# Sheet1.net
KiCad netlist of a schematic drawn in Altium Designer
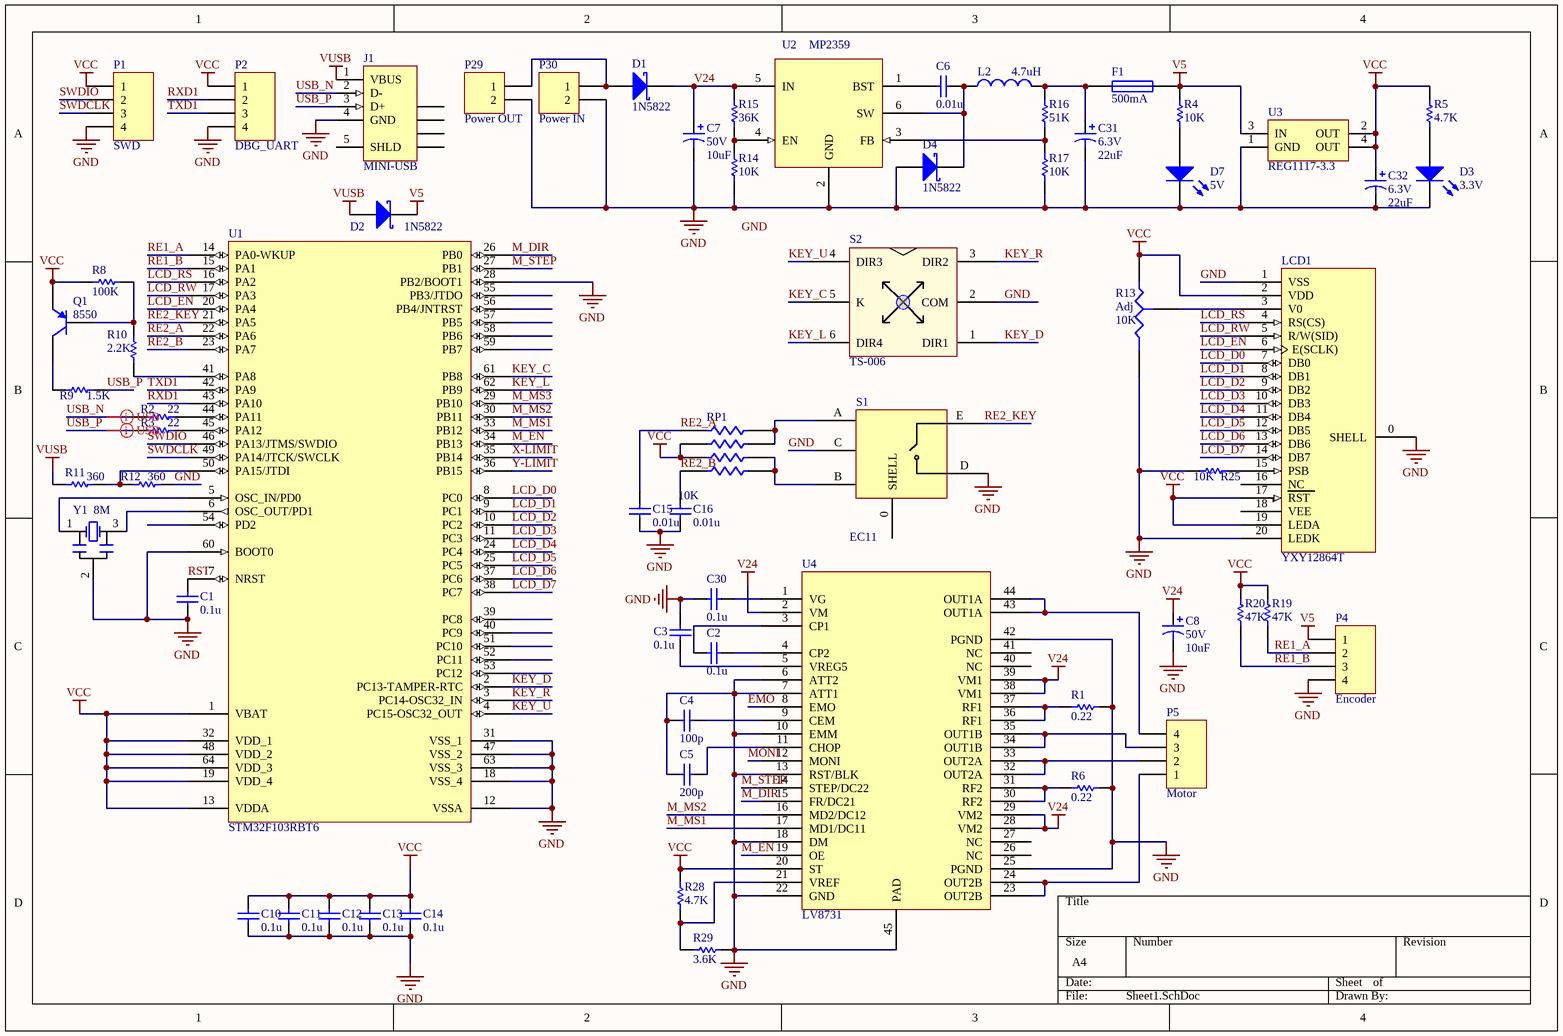
[diagram p0: Sheet1.SchDoc]

(export (version "E")
  (design (tool "Eeschema 10.0.6"))
  (components
    (comp (ref "C1")
      (value "0.1u")
      (footprint "C-1608[0603]")
      (description "Capacitor (Semiconductor SIM Model)")
      (fields (field (name "Comment") "Cap Semi") (field (name "PUBLISHER") "Altium Limited"))
      (libsource (lib "Miscellaneous Devices") (part "Cap Semi"))
    )
    (comp (ref "C2")
      (value "0.1u")
      (footprint "C-1608[0603]")
      (description "Capacitor (Semiconductor SIM Model)")
      (fields (field (name "Comment") "Cap Semi") (field (name "PUBLISHER") "Altium Limited"))
      (libsource (lib "Miscellaneous Devices") (part "Cap Semi"))
    )
    (comp (ref "C3")
      (value "0.1u")
      (footprint "C-1608[0603]")
      (description "Capacitor (Semiconductor SIM Model)")
      (fields (field (name "Comment") "Cap Semi") (field (name "PUBLISHER") "Altium Limited"))
      (libsource (lib "Miscellaneous Devices") (part "Cap Semi"))
    )
    (comp (ref "C4")
      (value "100p")
      (footprint "C-1608[0603]")
      (description "Capacitor (Semiconductor SIM Model)")
      (fields (field (name "Comment") "Cap Semi") (field (name "PUBLISHER") "Altium Limited"))
      (libsource (lib "Miscellaneous Devices") (part "Cap Semi"))
    )
    (comp (ref "C5")
      (value "200p")
      (footprint "C-1608[0603]")
      (description "Capacitor (Semiconductor SIM Model)")
      (fields (field (name "Comment") "Cap Semi") (field (name "PUBLISHER") "Altium Limited"))
      (libsource (lib "Miscellaneous Devices") (part "Cap Semi"))
    )
    (comp (ref "C6")
      (value "0.01u")
      (footprint "C-1608[0603]")
      (description "Capacitor (Semiconductor SIM Model)")
      (fields (field (name "Comment") "Cap Semi") (field (name "PUBLISHER") "Altium Limited"))
      (libsource (lib "Miscellaneous Devices") (part "Cap Semi"))
    )
    (comp (ref "C7")
      (value "50V")
      (footprint "RB.1/.25")
      (description "Polarized Capacitor (Radial)")
      (fields (field (name "ALTIUM_VALUE") "10uF") (field (name "PUBLISHER") "Altium Limited"))
      (libsource (lib "Miscellaneous Devices") (part "Cap Pol1"))
    )
    (comp (ref "C8")
      (value "50V")
      (footprint "RB.1/.25")
      (description "Polarized Capacitor (Radial)")
      (fields (field (name "ALTIUM_VALUE") "10uF") (field (name "PUBLISHER") "Altium Limited"))
      (libsource (lib "Miscellaneous Devices") (part "Cap Pol1"))
    )
    (comp (ref "C10")
      (value "0.1u")
      (footprint "C-1608[0603]")
      (description "Capacitor (Semiconductor SIM Model)")
      (fields (field (name "Comment") "Cap Semi") (field (name "PUBLISHER") "Altium Limited"))
      (libsource (lib "Miscellaneous Devices") (part "Cap Semi"))
    )
    (comp (ref "C11")
      (value "0.1u")
      (footprint "C-1608[0603]")
      (description "Capacitor (Semiconductor SIM Model)")
      (fields (field (name "Comment") "Cap Semi") (field (name "PUBLISHER") "Altium Limited"))
      (libsource (lib "Miscellaneous Devices") (part "Cap Semi"))
    )
    (comp (ref "C12")
      (value "0.1u")
      (footprint "C-1608[0603]")
      (description "Capacitor (Semiconductor SIM Model)")
      (fields (field (name "Comment") "Cap Semi") (field (name "PUBLISHER") "Altium Limited"))
      (libsource (lib "Miscellaneous Devices") (part "Cap Semi"))
    )
    (comp (ref "C13")
      (value "0.1u")
      (footprint "C-1608[0603]")
      (description "Capacitor (Semiconductor SIM Model)")
      (fields (field (name "Comment") "Cap Semi") (field (name "PUBLISHER") "Altium Limited"))
      (libsource (lib "Miscellaneous Devices") (part "Cap Semi"))
    )
    (comp (ref "C14")
      (value "0.1u")
      (footprint "C-1608[0603]")
      (description "Capacitor (Semiconductor SIM Model)")
      (fields (field (name "Comment") "Cap Semi") (field (name "PUBLISHER") "Altium Limited"))
      (libsource (lib "Miscellaneous Devices") (part "Cap Semi"))
    )
    (comp (ref "C15")
      (value "0.01u")
      (footprint "C-1608[0603]")
      (description "Capacitor (Semiconductor SIM Model)")
      (fields (field (name "Comment") "Cap Semi") (field (name "PUBLISHER") "Altium Limited"))
      (libsource (lib "Miscellaneous Devices") (part "Cap Semi"))
    )
    (comp (ref "C16")
      (value "0.01u")
      (footprint "C-1608[0603]")
      (description "Capacitor (Semiconductor SIM Model)")
      (fields (field (name "Comment") "Cap Semi") (field (name "PUBLISHER") "Altium Limited"))
      (libsource (lib "Miscellaneous Devices") (part "Cap Semi"))
    )
    (comp (ref "C30")
      (value "0.1u")
      (footprint "C-1608[0603]")
      (description "Capacitor (Semiconductor SIM Model)")
      (fields (field (name "Comment") "Cap Semi") (field (name "PUBLISHER") "Altium Limited"))
      (libsource (lib "Miscellaneous Devices") (part "Cap Semi"))
    )
    (comp (ref "C31")
      (value "6.3V")
      (footprint "C-2012[0805]")
      (description "Tantalum capacitor")
      (fields (field (name "ALTIUM_VALUE") "22uF") (field (name "PUBLISHER") "Altium Limited"))
      (libsource (lib "Miscellaneous Devices") (part "Cap Pol3"))
    )
    (comp (ref "C32")
      (value "6.3V")
      (footprint "C-2012[0805]")
      (description "Tantalum capacitor")
      (fields (field (name "ALTIUM_VALUE") "22uF") (field (name "PUBLISHER") "Altium Limited"))
      (libsource (lib "Miscellaneous Devices") (part "Cap Pol3"))
    )
    (comp (ref "D1")
      (value "1N5822")
      (footprint "DO-214AC")
      (description "Schottky Diode")
      (fields (field (name "PUBLISHER") "Altium Limited"))
      (libsource (lib "Miscellaneous Devices") (part "D Schottky"))
    )
    (comp (ref "D2")
      (value "1N5822")
      (footprint "DO-214AC")
      (description "Schottky Diode")
      (fields (field (name "PUBLISHER") "Altium Limited"))
      (libsource (lib "Miscellaneous Devices") (part "D Schottky"))
    )
    (comp (ref "D3")
      (value "3.3V")
      (footprint "LED_0805_RED")
      (description "Typical RED, GREEN, YELLOW, AMBER GaAs LED")
      (fields (field (name "PUBLISHER") "Altium Limited"))
      (libsource (lib "Miscellaneous Devices") (part "LED2"))
    )
    (comp (ref "D4")
      (value "1N5822")
      (footprint "DO-214AC")
      (description "Schottky Diode")
      (fields (field (name "PUBLISHER") "Altium Limited"))
      (libsource (lib "Miscellaneous Devices") (part "D Schottky"))
    )
    (comp (ref "D7")
      (value "5V")
      (footprint "LED_0805_RED")
      (description "Typical RED, GREEN, YELLOW, AMBER GaAs LED")
      (fields (field (name "PUBLISHER") "Altium Limited"))
      (libsource (lib "Miscellaneous Devices") (part "LED2"))
    )
    (comp (ref "F1")
      (value "500mA")
      (footprint "2012[0805]")
      (description "Fuse")
      (fields (field (name "PUBLISHER") "Altium Limited"))
      (libsource (lib "Miscellaneous Devices") (part "Fuse 1"))
    )
    (comp (ref "J1")
      (value "MINI-USB")
      (footprint "Mini USB 3D")
      (description "USB 2.0, Right Angle, SMT, A Type, Receptacle, 5 Position, Black")
      (fields (field (name "PUBLISHER") "Altium Limited"))
      (libsource (lib "AMP Serial Bus USB") (part "440478-1"))
    )
    (comp (ref "L2")
      (value "4.7uH")
      (footprint "L-5845")
      (description "Inductor")
      (fields (field (name "PUBLISHER") "Altium Limited"))
      (libsource (lib "Miscellaneous Devices") (part "Inductor"))
    )
    (comp (ref "LCD1")
      (value "YXY12864T")
      (footprint "12864T")
      (libsource (lib "Schlib1") (part "YXY12864T"))
    )
    (comp (ref "P1")
      (value "SWD")
      (footprint "HDR1X4")
      (description "Header, 4-Pin")
      (fields (field (name "PUBLISHER") "Altium Limited"))
      (libsource (lib "Miscellaneous Connectors") (part "Header 4"))
    )
    (comp (ref "P2")
      (value "DBG_UART")
      (footprint "HDR1X4")
      (description "Header, 4-Pin")
      (fields (field (name "PUBLISHER") "Altium Limited"))
      (libsource (lib "Miscellaneous Connectors") (part "Header 4"))
    )
    (comp (ref "P4")
      (value "Encoder")
      (footprint "HDR1X4H")
      (description "Header, 4-Pin, Right Angle")
      (fields (field (name "PUBLISHER") "Altium Limited"))
      (libsource (lib "Miscellaneous Connectors") (part "Header 4H"))
    )
    (comp (ref "P5")
      (value "Motor")
      (footprint "HDR1X4H")
      (description "Header, 4-Pin, Right Angle")
      (fields (field (name "PUBLISHER") "Altium Limited"))
      (libsource (lib "") (part "Header 4H_1"))
    )
    (comp (ref "P29")
      (value "Power OUT")
      (footprint "DC_POWER")
      (description "Header, 2-Pin")
      (fields (field (name "PUBLISHER") "Altium Limited"))
      (libsource (lib "Miscellaneous Connectors") (part "MHDR1X2"))
    )
    (comp (ref "P30")
      (value "Power IN")
      (footprint "DC_POWER")
      (description "Header, 2-Pin")
      (fields (field (name "PUBLISHER") "Altium Limited"))
      (libsource (lib "Miscellaneous Connectors") (part "MHDR1X2"))
    )
    (comp (ref "Q1")
      (value "8550")
      (footprint "SOT23B")
      (description "PNP Bipolar Transistor")
      (fields (field (name "PUBLISHER") "Altium Limited"))
      (libsource (lib "Miscellaneous Devices") (part "PNP"))
    )
    (comp (ref "R1")
      (value "0.22")
      (footprint "R-6332[2512]")
      (description "Semiconductor Resistor")
      (fields (field (name "Comment") "Res Semi") (field (name "PUBLISHER") "Altium Limited"))
      (libsource (lib "Miscellaneous Devices") (part "Res Semi"))
    )
    (comp (ref "R2")
      (value "22")
      (footprint "R-1608[0603]")
      (description "Semiconductor Resistor")
      (fields (field (name "Comment") "Res Semi") (field (name "PUBLISHER") "Altium Limited"))
      (libsource (lib "Miscellaneous Devices") (part "Res Semi"))
    )
    (comp (ref "R3")
      (value "22")
      (footprint "R-1608[0603]")
      (description "Semiconductor Resistor")
      (fields (field (name "Comment") "Res Semi") (field (name "PUBLISHER") "Altium Limited"))
      (libsource (lib "Miscellaneous Devices") (part "Res Semi"))
    )
    (comp (ref "R4")
      (value "10K")
      (footprint "R-1608[0603]")
      (description "Semiconductor Resistor")
      (fields (field (name "Comment") "Res Semi") (field (name "PUBLISHER") "Altium Limited"))
      (libsource (lib "Miscellaneous Devices") (part "Res Semi"))
    )
    (comp (ref "R5")
      (value "4.7K")
      (footprint "R-1608[0603]")
      (description "Semiconductor Resistor")
      (fields (field (name "Comment") "Res Semi") (field (name "PUBLISHER") "Altium Limited"))
      (libsource (lib "Miscellaneous Devices") (part "Res Semi"))
    )
    (comp (ref "R6")
      (value "0.22")
      (footprint "R-6332[2512]")
      (description "Semiconductor Resistor")
      (fields (field (name "Comment") "Res Semi") (field (name "PUBLISHER") "Altium Limited"))
      (libsource (lib "Miscellaneous Devices") (part "Res Semi"))
    )
    (comp (ref "R8")
      (value "100K")
      (footprint "R-1608[0603]")
      (description "Semiconductor Resistor")
      (fields (field (name "Comment") "Res Semi") (field (name "PUBLISHER") "Altium Limited"))
      (libsource (lib "Miscellaneous Devices") (part "Res Semi"))
    )
    (comp (ref "R9")
      (value "1.5K")
      (footprint "R-1608[0603]")
      (description "Semiconductor Resistor")
      (fields (field (name "Comment") "Res Semi") (field (name "PUBLISHER") "Altium Limited"))
      (libsource (lib "Miscellaneous Devices") (part "Res Semi"))
    )
    (comp (ref "R10")
      (value "2.2K")
      (footprint "R-1608[0603]")
      (description "Semiconductor Resistor")
      (fields (field (name "Comment") "Res Semi") (field (name "PUBLISHER") "Altium Limited"))
      (libsource (lib "Miscellaneous Devices") (part "Res Semi"))
    )
    (comp (ref "R11")
      (value "360")
      (footprint "R-1608[0603]")
      (description "Semiconductor Resistor")
      (fields (field (name "Comment") "Res Semi") (field (name "PUBLISHER") "Altium Limited"))
      (libsource (lib "Miscellaneous Devices") (part "Res Semi"))
    )
    (comp (ref "R12")
      (value "360")
      (footprint "R-1608[0603]")
      (description "Semiconductor Resistor")
      (fields (field (name "Comment") "Res Semi") (field (name "PUBLISHER") "Altium Limited"))
      (libsource (lib "Miscellaneous Devices") (part "Res Semi"))
    )
    (comp (ref "R13")
      (value "Adj")
      (footprint "HDR1X3")
      (description "Tapped Resistor")
      (fields (field (name "ALTIUM_VALUE") "10K") (field (name "PUBLISHER") "Altium Limited"))
      (libsource (lib "Miscellaneous Devices") (part "Res Tap"))
    )
    (comp (ref "R14")
      (value "10K")
      (footprint "R-1608[0603]")
      (description "Semiconductor Resistor")
      (fields (field (name "Comment") "Res Semi") (field (name "PUBLISHER") "Altium Limited"))
      (libsource (lib "Miscellaneous Devices") (part "Res Semi"))
    )
    (comp (ref "R15")
      (value "36K")
      (footprint "R-1608[0603]")
      (description "Semiconductor Resistor")
      (fields (field (name "Comment") "Res Semi") (field (name "PUBLISHER") "Altium Limited"))
      (libsource (lib "Miscellaneous Devices") (part "Res Semi"))
    )
    (comp (ref "R16")
      (value "51K")
      (footprint "R-1608[0603]")
      (description "Semiconductor Resistor")
      (fields (field (name "Comment") "Res Semi") (field (name "PUBLISHER") "Altium Limited"))
      (libsource (lib "Miscellaneous Devices") (part "Res Semi"))
    )
    (comp (ref "R17")
      (value "10K")
      (footprint "R-1608[0603]")
      (description "Semiconductor Resistor")
      (fields (field (name "Comment") "Res Semi") (field (name "PUBLISHER") "Altium Limited"))
      (libsource (lib "Miscellaneous Devices") (part "Res Semi"))
    )
    (comp (ref "R19")
      (value "47K")
      (footprint "R-1608[0603]")
      (description "Semiconductor Resistor")
      (fields (field (name "Comment") "Res Semi") (field (name "PUBLISHER") "Altium Limited"))
      (libsource (lib "Miscellaneous Devices") (part "Res Semi"))
    )
    (comp (ref "R20")
      (value "47K")
      (footprint "R-1608[0603]")
      (description "Semiconductor Resistor")
      (fields (field (name "Comment") "Res Semi") (field (name "PUBLISHER") "Altium Limited"))
      (libsource (lib "Miscellaneous Devices") (part "Res Semi"))
    )
    (comp (ref "R25")
      (value "10K")
      (footprint "R-1608[0603]")
      (description "Semiconductor Resistor")
      (fields (field (name "Comment") "Res Semi") (field (name "PUBLISHER") "Altium Limited"))
      (libsource (lib "Miscellaneous Devices") (part "Res Semi"))
    )
    (comp (ref "R28")
      (value "4.7K")
      (footprint "R-1608[0603]")
      (description "Semiconductor Resistor")
      (fields (field (name "Comment") "Res Semi") (field (name "PUBLISHER") "Altium Limited"))
      (libsource (lib "Miscellaneous Devices") (part "Res Semi"))
    )
    (comp (ref "R29")
      (value "3.6K")
      (footprint "R-1608[0603]")
      (description "Semiconductor Resistor")
      (fields (field (name "Comment") "Res Semi") (field (name "PUBLISHER") "Altium Limited"))
      (libsource (lib "Miscellaneous Devices") (part "Res Semi"))
    )
    (comp (ref "RP1")
      (value "10K")
      (footprint "R0603x4")
      (fields (field (name "Comment") "4xRes"))
      (libsource (lib "Schlib1") (part "RPACK4"))
    )
    (comp (ref "S1") (value "EC11") (footprint "EC11") (libsource (lib "Schlib1") (part "EC11")))
    (comp (ref "S2") (value "TS-006") (footprint "TS-006") (libsource (lib "Schlib1") (part "TS-006")))
    (comp (ref "U1")
      (value "STM32F103RBT6")
      (footprint "LQFP64_N")
      (description "STM32 ARM-based 32-bit MCU High-density")
      (fields (field (name "PUBLISHER") "Altium Limited"))
      (libsource (lib "ST Microcontroller 32-Bit STM32") (part "STM32F103RBT6"))
    )
    (comp (ref "U2")
      (value "MP2359")
      (footprint "SOT23-6")
      (description "1.2A, 24V, 1.4MHz  Step-Down Converter")
      (libsource (lib "Schlib1") (part "MP2359"))
    )
    (comp (ref "U3")
      (value "REG1117-3.3")
      (footprint "SOT223-3D")
      (description "800mA and 1A Low Dropout Positive Regulator 2.85V, 3.3V, 5V, and Adjustable")
      (fields (field (name "PUBLISHER") "Altium Limited"))
      (libsource (lib "BB Power Mgt Voltage Regulator") (part "REG1117-3.3"))
    )
    (comp (ref "U4") (value "LV8731") (footprint "LV8731_V3") (libsource (lib "Schlib1") (part "LV8731")))
    (comp (ref "Y1")
      (value "8M")
      (footprint "Crystal_C")
      (description "Crystal Oscillator")
      (fields (field (name "PUBLISHER") "Altium Limited"))
      (libsource (lib "Schlib1") (part "XTAL_C"))
    )
  )
  (nets
    (net (code "1") (name "/EMO") (class "Default")
      (node (ref "U4") (pin "8") (pinfunction "EMO_8") (pintype "passive"))
    )
    (net (code "2") (name "/KEY_C") (class "Default")
      (node (ref "S2") (pin "5") (pinfunction "K_5") (pintype "passive"))
      (node (ref "U1") (pin "61") (pinfunction "PB8_61") (pintype "bidirectional"))
    )
    (net (code "3") (name "/KEY_D") (class "Default")
      (node (ref "S2") (pin "1") (pinfunction "DIR1_1") (pintype "passive"))
      (node (ref "U1") (pin "2") (pinfunction "PC13-TAMPER-RTC_2") (pintype "bidirectional"))
    )
    (net (code "4") (name "/KEY_L") (class "Default")
      (node (ref "S2") (pin "6") (pinfunction "DIR4_6") (pintype "passive"))
      (node (ref "U1") (pin "62") (pinfunction "PB9_62") (pintype "bidirectional"))
    )
    (net (code "5") (name "/KEY_R") (class "Default")
      (node (ref "S2") (pin "3") (pinfunction "DIR2_3") (pintype "passive"))
      (node (ref "U1") (pin "3") (pinfunction "PC14-OSC32_IN_3") (pintype "bidirectional"))
    )
    (net (code "6") (name "/KEY_U") (class "Default")
      (node (ref "S2") (pin "4") (pinfunction "DIR3_4") (pintype "passive"))
      (node (ref "U1") (pin "4") (pinfunction "PC15-OSC32_OUT_4") (pintype "bidirectional"))
    )
    (net (code "7") (name "/LCD_D0") (class "Default")
      (node (ref "LCD1") (pin "7") (pinfunction "DB0_7") (pintype "bidirectional"))
      (node (ref "U1") (pin "8") (pinfunction "PC0_8") (pintype "bidirectional"))
    )
    (net (code "8") (name "/LCD_D1") (class "Default")
      (node (ref "LCD1") (pin "8") (pinfunction "DB1_8") (pintype "bidirectional"))
      (node (ref "U1") (pin "9") (pinfunction "PC1_9") (pintype "bidirectional"))
    )
    (net (code "9") (name "/LCD_D2") (class "Default")
      (node (ref "LCD1") (pin "9") (pinfunction "DB2_9") (pintype "bidirectional"))
      (node (ref "U1") (pin "10") (pinfunction "PC2_10") (pintype "bidirectional"))
    )
    (net (code "10") (name "/LCD_D3") (class "Default")
      (node (ref "LCD1") (pin "10") (pinfunction "DB3_10") (pintype "bidirectional"))
      (node (ref "U1") (pin "11") (pinfunction "PC3_11") (pintype "bidirectional"))
    )
    (net (code "11") (name "/LCD_D4") (class "Default")
      (node (ref "LCD1") (pin "11") (pinfunction "DB4_11") (pintype "bidirectional"))
      (node (ref "U1") (pin "24") (pinfunction "PC4_24") (pintype "bidirectional"))
    )
    (net (code "12") (name "/LCD_D5") (class "Default")
      (node (ref "LCD1") (pin "12") (pinfunction "DB5_12") (pintype "bidirectional"))
      (node (ref "U1") (pin "25") (pinfunction "PC5_25") (pintype "bidirectional"))
    )
    (net (code "13") (name "/LCD_D6") (class "Default")
      (node (ref "LCD1") (pin "13") (pinfunction "DB6_13") (pintype "bidirectional"))
      (node (ref "U1") (pin "37") (pinfunction "PC6_37") (pintype "bidirectional"))
    )
    (net (code "14") (name "/LCD_D7") (class "Default")
      (node (ref "LCD1") (pin "14") (pinfunction "DB7_14") (pintype "bidirectional"))
      (node (ref "U1") (pin "38") (pinfunction "PC7_38") (pintype "bidirectional"))
    )
    (net (code "15") (name "/LCD_EN") (class "Default")
      (node (ref "LCD1") (pin "6") (pinfunction "E(SCLK)_6") (pintype "input"))
      (node (ref "U1") (pin "20") (pinfunction "PA4_20") (pintype "bidirectional"))
    )
    (net (code "16") (name "/LCD_RS") (class "Default")
      (node (ref "LCD1") (pin "4") (pinfunction "RS(CS)_4") (pintype "input"))
      (node (ref "U1") (pin "16") (pinfunction "PA2_16") (pintype "bidirectional"))
    )
    (net (code "17") (name "/LCD_RW") (class "Default")
      (node (ref "LCD1") (pin "5") (pinfunction "R/W(SID)_5") (pintype "input"))
      (node (ref "U1") (pin "17") (pinfunction "PA3_17") (pintype "bidirectional"))
    )
    (net (code "18") (name "/MONI") (class "Default")
      (node (ref "U4") (pin "12") (pinfunction "MONI_12") (pintype "passive"))
    )
    (net (code "19") (name "/M_DIR") (class "Default")
      (node (ref "U1") (pin "26") (pinfunction "PB0_26") (pintype "bidirectional"))
      (node (ref "U4") (pin "15") (pinfunction "FR/DC21_15") (pintype "passive"))
    )
    (net (code "20") (name "/M_EN") (class "Default")
      (node (ref "U1") (pin "34") (pinfunction "PB13_34") (pintype "bidirectional"))
      (node (ref "U4") (pin "19") (pinfunction "OE_19") (pintype "passive"))
    )
    (net (code "21") (name "/M_MS1") (class "Default")
      (node (ref "U1") (pin "33") (pinfunction "PB12_33") (pintype "bidirectional"))
      (node (ref "U4") (pin "17") (pinfunction "MD1/DC11_17") (pintype "passive"))
    )
    (net (code "22") (name "/M_MS2") (class "Default")
      (node (ref "U1") (pin "30") (pinfunction "PB11_30") (pintype "bidirectional"))
      (node (ref "U4") (pin "16") (pinfunction "MD2/DC12_16") (pintype "passive"))
    )
    (net (code "23") (name "/M_MS3") (class "Default")
      (node (ref "U1") (pin "29") (pinfunction "PB10_29") (pintype "bidirectional"))
    )
    (net (code "24") (name "/M_STEP") (class "Default")
      (node (ref "U1") (pin "27") (pinfunction "PB1_27") (pintype "bidirectional"))
      (node (ref "U4") (pin "14") (pinfunction "STEP/DC22_14") (pintype "passive"))
    )
    (net (code "25") (name "/RE1_A") (class "Default")
      (node (ref "P4") (pin "2") (pinfunction "2_2") (pintype "passive"))
      (node (ref "R19") (pin "1") (pinfunction "1_1") (pintype "passive"))
      (node (ref "U1") (pin "14") (pinfunction "PA0-WKUP_14") (pintype "bidirectional"))
    )
    (net (code "26") (name "/RE1_B") (class "Default")
      (node (ref "P4") (pin "3") (pinfunction "3_3") (pintype "passive"))
      (node (ref "R20") (pin "1") (pinfunction "1_1") (pintype "passive"))
      (node (ref "U1") (pin "15") (pinfunction "PA1_15") (pintype "bidirectional"))
    )
    (net (code "27") (name "/RE2_A") (class "Default")
      (node (ref "C15") (pin "2") (pinfunction "2_2") (pintype "passive"))
      (node (ref "RP1") (pin "5") (pinfunction "5_5") (pintype "passive"))
      (node (ref "U1") (pin "22") (pinfunction "PA6_22") (pintype "bidirectional"))
    )
    (net (code "28") (name "/RE2_B") (class "Default")
      (node (ref "C16") (pin "2") (pinfunction "2_2") (pintype "passive"))
      (node (ref "RP1") (pin "8") (pinfunction "8_8") (pintype "passive"))
      (node (ref "U1") (pin "23") (pinfunction "PA7_23") (pintype "bidirectional"))
    )
    (net (code "29") (name "/RE2_KEY") (class "Default")
      (node (ref "S1") (pin "E") (pinfunction "25_E") (pintype "passive"))
      (node (ref "U1") (pin "21") (pinfunction "PA5_21") (pintype "bidirectional"))
    )
    (net (code "30") (name "/RST") (class "Default")
      (node (ref "C1") (pin "2") (pinfunction "2_2") (pintype "passive"))
      (node (ref "U1") (pin "7") (pinfunction "NRST_7") (pintype "bidirectional"))
    )
    (net (code "31") (name "/RXD1") (class "Default")
      (node (ref "P2") (pin "2") (pinfunction "2_2") (pintype "passive"))
      (node (ref "U1") (pin "43") (pinfunction "PA10_43") (pintype "bidirectional"))
    )
    (net (code "32") (name "/SWDCLK") (class "Default")
      (node (ref "P1") (pin "3") (pinfunction "3_3") (pintype "passive"))
      (node (ref "U1") (pin "49") (pinfunction "PA14/JTCK/SWCLK_49") (pintype "bidirectional"))
    )
    (net (code "33") (name "/SWDIO") (class "Default")
      (node (ref "P1") (pin "2") (pinfunction "2_2") (pintype "passive"))
      (node (ref "U1") (pin "46") (pinfunction "PA13/JTMS/SWDIO_46") (pintype "bidirectional"))
    )
    (net (code "34") (name "/TXD1") (class "Default")
      (node (ref "P2") (pin "3") (pinfunction "3_3") (pintype "passive"))
      (node (ref "U1") (pin "42") (pinfunction "PA9_42") (pintype "bidirectional"))
    )
    (net (code "35") (name "/USB_N") (class "Default")
      (node (ref "J1") (pin "2") (pinfunction "D-_2") (pintype "input"))
      (node (ref "R2") (pin "1") (pinfunction "1_1") (pintype "passive"))
    )
    (net (code "36") (name "/USB_P") (class "Default")
      (node (ref "J1") (pin "3") (pinfunction "D+_3") (pintype "input"))
      (node (ref "R3") (pin "1") (pinfunction "1_1") (pintype "passive"))
      (node (ref "R9") (pin "1") (pinfunction "1_1") (pintype "passive"))
    )
    (net (code "37") (name "/X-LIMIT") (class "Default")
      (node (ref "U1") (pin "35") (pinfunction "PB14_35") (pintype "bidirectional"))
    )
    (net (code "38") (name "/Y-LIMIT") (class "Default")
      (node (ref "U1") (pin "36") (pinfunction "PB15_36") (pintype "bidirectional"))
    )
    (net (code "39") (name "GND") (class "Default")
      (node (ref "C1") (pin "1") (pinfunction "1_1") (pintype "passive"))
      (node (ref "C10") (pin "1") (pinfunction "1_1") (pintype "passive"))
      (node (ref "C11") (pin "1") (pinfunction "1_1") (pintype "passive"))
      (node (ref "C12") (pin "1") (pinfunction "1_1") (pintype "passive"))
      (node (ref "C13") (pin "1") (pinfunction "1_1") (pintype "passive"))
      (node (ref "C14") (pin "1") (pinfunction "1_1") (pintype "passive"))
      (node (ref "C15") (pin "1") (pinfunction "1_1") (pintype "passive"))
      (node (ref "C16") (pin "1") (pinfunction "1_1") (pintype "passive"))
      (node (ref "C3") (pin "2") (pinfunction "2_2") (pintype "passive"))
      (node (ref "C30") (pin "2") (pinfunction "2_2") (pintype "passive"))
      (node (ref "C31") (pin "2") (pinfunction "2_2") (pintype "passive"))
      (node (ref "C32") (pin "2") (pinfunction "2_2") (pintype "passive"))
      (node (ref "C4") (pin "1") (pinfunction "1_1") (pintype "passive"))
      (node (ref "C5") (pin "1") (pinfunction "1_1") (pintype "passive"))
      (node (ref "C7") (pin "2") (pinfunction "2_2") (pintype "passive"))
      (node (ref "C8") (pin "2") (pinfunction "2_2") (pintype "passive"))
      (node (ref "D3") (pin "2") (pinfunction "K_2") (pintype "passive"))
      (node (ref "D4") (pin "1") (pinfunction "A_1") (pintype "passive"))
      (node (ref "D7") (pin "2") (pinfunction "K_2") (pintype "passive"))
      (node (ref "J1") (pin "4") (pinfunction "GND_4") (pintype "power_in"))
      (node (ref "LCD1") (pin "0") (pinfunction "SHELL_0") (pintype "power_in"))
      (node (ref "LCD1") (pin "1") (pinfunction "VSS_1") (pintype "power_in"))
      (node (ref "LCD1") (pin "20") (pinfunction "LEDK_20") (pintype "power_in"))
      (node (ref "P1") (pin "4") (pinfunction "4_4") (pintype "passive"))
      (node (ref "P2") (pin "4") (pinfunction "4_4") (pintype "passive"))
      (node (ref "P29") (pin "2") (pinfunction "2_2") (pintype "passive"))
      (node (ref "P30") (pin "2") (pinfunction "2_2") (pintype "passive"))
      (node (ref "P4") (pin "4") (pinfunction "4_4") (pintype "passive"))
      (node (ref "R1") (pin "1") (pinfunction "1_1") (pintype "passive"))
      (node (ref "R12") (pin "1") (pinfunction "1_1") (pintype "passive"))
      (node (ref "R13") (pin "2") (pinfunction "B_2") (pintype "passive"))
      (node (ref "R14") (pin "1") (pinfunction "1_1") (pintype "passive"))
      (node (ref "R17") (pin "1") (pinfunction "1_1") (pintype "passive"))
      (node (ref "R25") (pin "2") (pinfunction "2_2") (pintype "passive"))
      (node (ref "R29") (pin "1") (pinfunction "1_1") (pintype "passive"))
      (node (ref "R6") (pin "1") (pinfunction "1_1") (pintype "passive"))
      (node (ref "S1") (pin "C") (pinfunction "C_C") (pintype "passive"))
      (node (ref "S1") (pin "D") (pinfunction "D_D") (pintype "passive"))
      (node (ref "S2") (pin "2") (pinfunction "COM_2") (pintype "passive"))
      (node (ref "U1") (pin "12") (pinfunction "VSSA_12") (pintype "power_in"))
      (node (ref "U1") (pin "18") (pinfunction "VSS_4_18") (pintype "power_in"))
      (node (ref "U1") (pin "28") (pinfunction "PB2/BOOT1_28") (pintype "bidirectional"))
      (node (ref "U1") (pin "31") (pinfunction "VSS_1_31") (pintype "power_in"))
      (node (ref "U1") (pin "47") (pinfunction "VSS_2_47") (pintype "power_in"))
      (node (ref "U1") (pin "60") (pinfunction "BOOT0_60") (pintype "input"))
      (node (ref "U1") (pin "63") (pinfunction "VSS_3_63") (pintype "power_in"))
      (node (ref "U2") (pin "2") (pinfunction "GND_2") (pintype "passive"))
      (node (ref "U3") (pin "1") (pinfunction "GND_1") (pintype "power_in"))
      (node (ref "U4") (pin "10") (pinfunction "EMM_10") (pintype "passive"))
      (node (ref "U4") (pin "13") (pinfunction "RST/BLK_13") (pintype "passive"))
      (node (ref "U4") (pin "18") (pinfunction "DM_18") (pintype "passive"))
      (node (ref "U4") (pin "22") (pinfunction "GND_22") (pintype "passive"))
      (node (ref "U4") (pin "25") (pinfunction "PGND_25") (pintype "passive"))
      (node (ref "U4") (pin "42") (pinfunction "PGND_42") (pintype "passive"))
      (node (ref "U4") (pin "45") (pinfunction "PAD_45") (pintype "passive"))
      (node (ref "U4") (pin "6") (pinfunction "ATT2_6") (pintype "passive"))
      (node (ref "U4") (pin "7") (pinfunction "ATT1_7") (pintype "passive"))
      (node (ref "Y1") (pin "2") (pinfunction "GND_2") (pintype "passive"))
    )
    (net (code "40") (name "Net-(C31-Pad1)") (class "Default")
      (node (ref "C31") (pin "1") (pinfunction "1_1") (pintype "passive"))
      (node (ref "F1") (pin "2") (pinfunction "2_2") (pintype "passive"))
      (node (ref "L2") (pin "2") (pinfunction "2_2") (pintype "passive"))
      (node (ref "R16") (pin "2") (pinfunction "2_2") (pintype "passive"))
    )
    (net (code "41") (name "Net-(D1-A)") (class "Default")
      (node (ref "D1") (pin "1") (pinfunction "A_1") (pintype "passive"))
      (node (ref "P29") (pin "1") (pinfunction "1_1") (pintype "passive"))
      (node (ref "P30") (pin "1") (pinfunction "1_1") (pintype "passive"))
    )
    (net (code "42") (name "Net-(D3-A)") (class "Default")
      (node (ref "D3") (pin "1") (pinfunction "A_1") (pintype "passive"))
      (node (ref "R5") (pin "2") (pinfunction "2_2") (pintype "passive"))
    )
    (net (code "43") (name "Net-(D4-K)") (class "Default")
      (node (ref "C6") (pin "1") (pinfunction "1_1") (pintype "passive"))
      (node (ref "D4") (pin "2") (pinfunction "K_2") (pintype "passive"))
      (node (ref "L2") (pin "1") (pinfunction "1_1") (pintype "passive"))
      (node (ref "U2") (pin "6") (pinfunction "SW_6") (pintype "power_in"))
    )
    (net (code "44") (name "Net-(D7-A)") (class "Default")
      (node (ref "D7") (pin "1") (pinfunction "A_1") (pintype "passive"))
      (node (ref "R4") (pin "1") (pinfunction "1_1") (pintype "passive"))
    )
    (net (code "45") (name "Net-(LCD1-PSB)") (class "Default")
      (node (ref "LCD1") (pin "15") (pinfunction "PSB_15") (pintype "input"))
      (node (ref "R25") (pin "1") (pinfunction "1_1") (pintype "passive"))
    )
    (net (code "46") (name "Net-(LCD1-V0)") (class "Default")
      (node (ref "LCD1") (pin "3") (pinfunction "V0_3") (pintype "power_in"))
      (node (ref "R13") (pin "3") (pinfunction "TAP_3") (pintype "passive"))
    )
    (net (code "47") (name "Net-(P5-Pad1)") (class "Default")
      (node (ref "P5") (pin "1") (pinfunction "1_1") (pintype "passive"))
      (node (ref "U4") (pin "23") (pinfunction "OUT2B_23") (pintype "passive"))
      (node (ref "U4") (pin "24") (pinfunction "OUT2B_24") (pintype "passive"))
    )
    (net (code "48") (name "Net-(P5-Pad2)") (class "Default")
      (node (ref "P5") (pin "2") (pinfunction "2_2") (pintype "passive"))
      (node (ref "U4") (pin "32") (pinfunction "OUT2A_32") (pintype "passive"))
      (node (ref "U4") (pin "33") (pinfunction "OUT2A_33") (pintype "passive"))
    )
    (net (code "49") (name "Net-(P5-Pad3)") (class "Default")
      (node (ref "P5") (pin "3") (pinfunction "3_3") (pintype "passive"))
      (node (ref "U4") (pin "34") (pinfunction "OUT1B_34") (pintype "passive"))
      (node (ref "U4") (pin "35") (pinfunction "OUT1B_35") (pintype "passive"))
    )
    (net (code "50") (name "Net-(P5-Pad4)") (class "Default")
      (node (ref "P5") (pin "4") (pinfunction "4_4") (pintype "passive"))
      (node (ref "U4") (pin "43") (pinfunction "OUT1A_43") (pintype "passive"))
      (node (ref "U4") (pin "44") (pinfunction "OUT1A_44") (pintype "passive"))
    )
    (net (code "51") (name "Net-(Q1-B)") (class "Default")
      (node (ref "Q1") (pin "2") (pinfunction "B_2") (pintype "passive"))
      (node (ref "R10") (pin "2") (pinfunction "2_2") (pintype "passive"))
      (node (ref "R8") (pin "1") (pinfunction "1_1") (pintype "passive"))
    )
    (net (code "52") (name "Net-(Q1-C)") (class "Default")
      (node (ref "Q1") (pin "1") (pinfunction "C_1") (pintype "passive"))
      (node (ref "R9") (pin "2") (pinfunction "2_2") (pintype "passive"))
    )
    (net (code "53") (name "Net-(R1-Pad2)") (class "Default")
      (node (ref "R1") (pin "2") (pinfunction "2_2") (pintype "passive"))
      (node (ref "U4") (pin "36") (pinfunction "RF1_36") (pintype "passive"))
      (node (ref "U4") (pin "37") (pinfunction "RF1_37") (pintype "passive"))
    )
    (net (code "54") (name "Net-(R6-Pad2)") (class "Default")
      (node (ref "R6") (pin "2") (pinfunction "2_2") (pintype "passive"))
      (node (ref "U4") (pin "30") (pinfunction "RF2_30") (pintype "passive"))
      (node (ref "U4") (pin "31") (pinfunction "RF2_31") (pintype "passive"))
    )
    (net (code "55") (name "Net-(RP1-Pad1)") (class "Default")
      (node (ref "RP1") (pin "1") (pinfunction "1_1") (pintype "passive"))
      (node (ref "RP1") (pin "2") (pinfunction "2_2") (pintype "passive"))
      (node (ref "S1") (pin "B") (pinfunction "B_B") (pintype "passive"))
    )
    (net (code "56") (name "Net-(RP1-Pad3)") (class "Default")
      (node (ref "RP1") (pin "3") (pinfunction "3_3") (pintype "passive"))
      (node (ref "RP1") (pin "4") (pinfunction "4_4") (pintype "passive"))
      (node (ref "S1") (pin "A") (pinfunction "A_A") (pintype "passive"))
    )
    (net (code "57") (name "Net-(U1-OSC_IN{slash}PD0)") (class "Default")
      (node (ref "U1") (pin "5") (pinfunction "OSC_IN/PD0_5") (pintype "input"))
      (node (ref "Y1") (pin "1") (pinfunction "OSC1_1") (pintype "passive"))
    )
    (net (code "58") (name "Net-(U1-OSC_OUT{slash}PD1)") (class "Default")
      (node (ref "U1") (pin "6") (pinfunction "OSC_OUT/PD1_6") (pintype "output"))
      (node (ref "Y1") (pin "3") (pinfunction "OSC2_3") (pintype "passive"))
    )
    (net (code "59") (name "Net-(U1-PA8)") (class "Default")
      (node (ref "R10") (pin "1") (pinfunction "1_1") (pintype "passive"))
      (node (ref "U1") (pin "41") (pinfunction "PA8_41") (pintype "bidirectional"))
    )
    (net (code "60") (name "Net-(U1-PA11)") (class "Default")
      (node (ref "R2") (pin "2") (pinfunction "2_2") (pintype "passive"))
      (node (ref "U1") (pin "44") (pinfunction "PA11_44") (pintype "bidirectional"))
    )
    (net (code "61") (name "Net-(U1-PA12)") (class "Default")
      (node (ref "R3") (pin "2") (pinfunction "2_2") (pintype "passive"))
      (node (ref "U1") (pin "45") (pinfunction "PA12_45") (pintype "bidirectional"))
    )
    (net (code "62") (name "Net-(U1-PA15{slash}JTDI)") (class "Default")
      (node (ref "R11") (pin "1") (pinfunction "1_1") (pintype "passive"))
      (node (ref "R12") (pin "2") (pinfunction "2_2") (pintype "passive"))
      (node (ref "U1") (pin "50") (pinfunction "PA15/JTDI_50") (pintype "bidirectional"))
    )
    (net (code "63") (name "Net-(U2-BST)") (class "Default")
      (node (ref "C6") (pin "2") (pinfunction "2_2") (pintype "passive"))
      (node (ref "U2") (pin "1") (pinfunction "BST_1") (pintype "passive"))
    )
    (net (code "64") (name "Net-(U2-EN)") (class "Default")
      (node (ref "R14") (pin "2") (pinfunction "2_2") (pintype "passive"))
      (node (ref "R15") (pin "1") (pinfunction "1_1") (pintype "passive"))
      (node (ref "U2") (pin "4") (pinfunction "EN_4") (pintype "input"))
    )
    (net (code "65") (name "Net-(U2-FB)") (class "Default")
      (node (ref "R16") (pin "1") (pinfunction "1_1") (pintype "passive"))
      (node (ref "R17") (pin "2") (pinfunction "2_2") (pintype "passive"))
      (node (ref "U2") (pin "3") (pinfunction "FB_3") (pintype "input"))
    )
    (net (code "66") (name "Net-(U4-CEM)") (class "Default")
      (node (ref "C4") (pin "2") (pinfunction "2_2") (pintype "passive"))
      (node (ref "U4") (pin "9") (pinfunction "CEM_9") (pintype "passive"))
    )
    (net (code "67") (name "Net-(U4-CHOP)") (class "Default")
      (node (ref "C5") (pin "2") (pinfunction "2_2") (pintype "passive"))
      (node (ref "U4") (pin "11") (pinfunction "CHOP_11") (pintype "passive"))
    )
    (net (code "68") (name "Net-(U4-CP1)") (class "Default")
      (node (ref "C2") (pin "2") (pinfunction "2_2") (pintype "passive"))
      (node (ref "U4") (pin "3") (pinfunction "CP1_3") (pintype "passive"))
    )
    (net (code "69") (name "Net-(U4-CP2)") (class "Default")
      (node (ref "C2") (pin "1") (pinfunction "1_1") (pintype "passive"))
      (node (ref "U4") (pin "4") (pinfunction "CP2_4") (pintype "passive"))
    )
    (net (code "70") (name "Net-(U4-VG)") (class "Default")
      (node (ref "C30") (pin "1") (pinfunction "1_1") (pintype "passive"))
      (node (ref "U4") (pin "1") (pinfunction "VG_1") (pintype "passive"))
    )
    (net (code "71") (name "Net-(U4-VREF)") (class "Default")
      (node (ref "R28") (pin "1") (pinfunction "1_1") (pintype "passive"))
      (node (ref "R29") (pin "2") (pinfunction "2_2") (pintype "passive"))
      (node (ref "U4") (pin "21") (pinfunction "VREF_21") (pintype "passive"))
    )
    (net (code "72") (name "Net-(U4-VREG5)") (class "Default")
      (node (ref "C3") (pin "1") (pinfunction "1_1") (pintype "passive"))
      (node (ref "U4") (pin "5") (pinfunction "VREG5_5") (pintype "passive"))
    )
    (net (code "73") (name "V5") (class "Default")
      (node (ref "D2") (pin "2") (pinfunction "K_2") (pintype "passive"))
      (node (ref "F1") (pin "1") (pinfunction "1_1") (pintype "passive"))
      (node (ref "P4") (pin "1") (pinfunction "1_1") (pintype "passive"))
      (node (ref "R4") (pin "2") (pinfunction "2_2") (pintype "passive"))
      (node (ref "U3") (pin "3") (pinfunction "IN_3") (pintype "power_in"))
    )
    (net (code "74") (name "V24") (class "Default")
      (node (ref "C7") (pin "1") (pinfunction "1_1") (pintype "passive"))
      (node (ref "C8") (pin "1") (pinfunction "1_1") (pintype "passive"))
      (node (ref "D1") (pin "2") (pinfunction "K_2") (pintype "passive"))
      (node (ref "R15") (pin "2") (pinfunction "2_2") (pintype "passive"))
      (node (ref "U2") (pin "5") (pinfunction "IN_5") (pintype "power_in"))
      (node (ref "U4") (pin "2") (pinfunction "VM_2") (pintype "passive"))
      (node (ref "U4") (pin "28") (pinfunction "VM2_28") (pintype "passive"))
      (node (ref "U4") (pin "29") (pinfunction "VM2_29") (pintype "passive"))
      (node (ref "U4") (pin "38") (pinfunction "VM1_38") (pintype "passive"))
      (node (ref "U4") (pin "39") (pinfunction "VM1_39") (pintype "passive"))
    )
    (net (code "75") (name "VCC") (class "Default")
      (node (ref "C10") (pin "2") (pinfunction "2_2") (pintype "passive"))
      (node (ref "C11") (pin "2") (pinfunction "2_2") (pintype "passive"))
      (node (ref "C12") (pin "2") (pinfunction "2_2") (pintype "passive"))
      (node (ref "C13") (pin "2") (pinfunction "2_2") (pintype "passive"))
      (node (ref "C14") (pin "2") (pinfunction "2_2") (pintype "passive"))
      (node (ref "C32") (pin "1") (pinfunction "1_1") (pintype "passive"))
      (node (ref "LCD1") (pin "17") (pinfunction "RST_17") (pintype "input"))
      (node (ref "LCD1") (pin "19") (pinfunction "LEDA_19") (pintype "power_in"))
      (node (ref "LCD1") (pin "2") (pinfunction "VDD_2") (pintype "power_in"))
      (node (ref "P1") (pin "1") (pinfunction "1_1") (pintype "passive"))
      (node (ref "P2") (pin "1") (pinfunction "1_1") (pintype "passive"))
      (node (ref "Q1") (pin "3") (pinfunction "E_3") (pintype "passive"))
      (node (ref "R13") (pin "1") (pinfunction "A_1") (pintype "passive"))
      (node (ref "R19") (pin "2") (pinfunction "2_2") (pintype "passive"))
      (node (ref "R20") (pin "2") (pinfunction "2_2") (pintype "passive"))
      (node (ref "R28") (pin "2") (pinfunction "2_2") (pintype "passive"))
      (node (ref "R5") (pin "1") (pinfunction "1_1") (pintype "passive"))
      (node (ref "R8") (pin "2") (pinfunction "2_2") (pintype "passive"))
      (node (ref "RP1") (pin "6") (pinfunction "6_6") (pintype "passive"))
      (node (ref "RP1") (pin "7") (pinfunction "7_7") (pintype "passive"))
      (node (ref "U1") (pin "1") (pinfunction "VBAT_1") (pintype "power_in"))
      (node (ref "U1") (pin "13") (pinfunction "VDDA_13") (pintype "power_in"))
      (node (ref "U1") (pin "19") (pinfunction "VDD_4_19") (pintype "power_in"))
      (node (ref "U1") (pin "32") (pinfunction "VDD_1_32") (pintype "power_in"))
      (node (ref "U1") (pin "48") (pinfunction "VDD_2_48") (pintype "power_in"))
      (node (ref "U1") (pin "64") (pinfunction "VDD_3_64") (pintype "power_in"))
      (node (ref "U3") (pin "2") (pinfunction "OUT_2") (pintype "power_in"))
      (node (ref "U3") (pin "4") (pinfunction "OUT_4") (pintype "power_in"))
      (node (ref "U4") (pin "20") (pinfunction "ST_20") (pintype "passive"))
    )
    (net (code "76") (name "VUSB") (class "Default")
      (node (ref "D2") (pin "1") (pinfunction "A_1") (pintype "passive"))
      (node (ref "J1") (pin "1") (pinfunction "VBUS_1") (pintype "power_in"))
      (node (ref "R11") (pin "2") (pinfunction "2_2") (pintype "passive"))
    )
    (net (code "77") (name "unconnected-(J1-SHLD-Pad5)") (class "Default")
      (node (ref "J1") (pin "5") (pinfunction "SHLD_5") (pintype "passive"))
    )
    (net (code "78") (name "unconnected-(J1-SHLD-Pad6)") (class "Default")
      (node (ref "J1") (pin "6") (pinfunction "SHLD_6") (pintype "passive"))
    )
    (net (code "79") (name "unconnected-(J1-SHLD-Pad7)") (class "Default")
      (node (ref "J1") (pin "7") (pinfunction "SHLD_7") (pintype "passive"))
    )
    (net (code "80") (name "unconnected-(J1-SHLD-Pad8)") (class "Default")
      (node (ref "J1") (pin "8") (pinfunction "SHLD_8") (pintype "passive"))
    )
    (net (code "81") (name "unconnected-(J1-SHLD-Pad9)") (class "Default")
      (node (ref "J1") (pin "9") (pinfunction "SHLD_9") (pintype "passive"))
    )
    (net (code "82") (name "unconnected-(LCD1-NC-Pad16)") (class "Default")
      (node (ref "LCD1") (pin "16") (pinfunction "NC_16") (pintype "passive"))
    )
    (net (code "83") (name "unconnected-(LCD1-VEE-Pad18)") (class "Default")
      (node (ref "LCD1") (pin "18") (pinfunction "VEE_18") (pintype "power_in"))
    )
    (net (code "84") (name "unconnected-(S1-SHELL-Pad0)") (class "Default")
      (node (ref "S1") (pin "0") (pinfunction "SHELL_0") (pintype "passive"))
    )
    (net (code "85") (name "unconnected-(U1-PB3{slash}JTDO-Pad55)") (class "Default")
      (node (ref "U1") (pin "55") (pinfunction "PB3/JTDO_55") (pintype "bidirectional"))
    )
    (net (code "86") (name "unconnected-(U1-PB4{slash}JNTRST-Pad56)") (class "Default")
      (node (ref "U1") (pin "56") (pinfunction "PB4/JNTRST_56") (pintype "bidirectional"))
    )
    (net (code "87") (name "unconnected-(U1-PB5-Pad57)") (class "Default")
      (node (ref "U1") (pin "57") (pinfunction "PB5_57") (pintype "bidirectional"))
    )
    (net (code "88") (name "unconnected-(U1-PB6-Pad58)") (class "Default")
      (node (ref "U1") (pin "58") (pinfunction "PB6_58") (pintype "bidirectional"))
    )
    (net (code "89") (name "unconnected-(U1-PB7-Pad59)") (class "Default")
      (node (ref "U1") (pin "59") (pinfunction "PB7_59") (pintype "bidirectional"))
    )
    (net (code "90") (name "unconnected-(U1-PC8-Pad39)") (class "Default")
      (node (ref "U1") (pin "39") (pinfunction "PC8_39") (pintype "bidirectional"))
    )
    (net (code "91") (name "unconnected-(U1-PC9-Pad40)") (class "Default")
      (node (ref "U1") (pin "40") (pinfunction "PC9_40") (pintype "bidirectional"))
    )
    (net (code "92") (name "unconnected-(U1-PC10-Pad51)") (class "Default")
      (node (ref "U1") (pin "51") (pinfunction "PC10_51") (pintype "bidirectional"))
    )
    (net (code "93") (name "unconnected-(U1-PC11-Pad52)") (class "Default")
      (node (ref "U1") (pin "52") (pinfunction "PC11_52") (pintype "bidirectional"))
    )
    (net (code "94") (name "unconnected-(U1-PC12-Pad53)") (class "Default")
      (node (ref "U1") (pin "53") (pinfunction "PC12_53") (pintype "bidirectional"))
    )
    (net (code "95") (name "unconnected-(U1-PD2-Pad54)") (class "Default")
      (node (ref "U1") (pin "54") (pinfunction "PD2_54") (pintype "bidirectional"))
    )
    (net (code "96") (name "unconnected-(U4-NC-Pad26)") (class "Default")
      (node (ref "U4") (pin "26") (pinfunction "NC_26") (pintype "passive"))
    )
    (net (code "97") (name "unconnected-(U4-NC-Pad27)") (class "Default")
      (node (ref "U4") (pin "27") (pinfunction "NC_27") (pintype "passive"))
    )
    (net (code "98") (name "unconnected-(U4-NC-Pad40)") (class "Default")
      (node (ref "U4") (pin "40") (pinfunction "NC_40") (pintype "passive"))
    )
    (net (code "99") (name "unconnected-(U4-NC-Pad41)") (class "Default")
      (node (ref "U4") (pin "41") (pinfunction "NC_41") (pintype "passive"))
    )
  )
)
